# Schematic.net
KiCad netlist of a schematic drawn in EAGLE
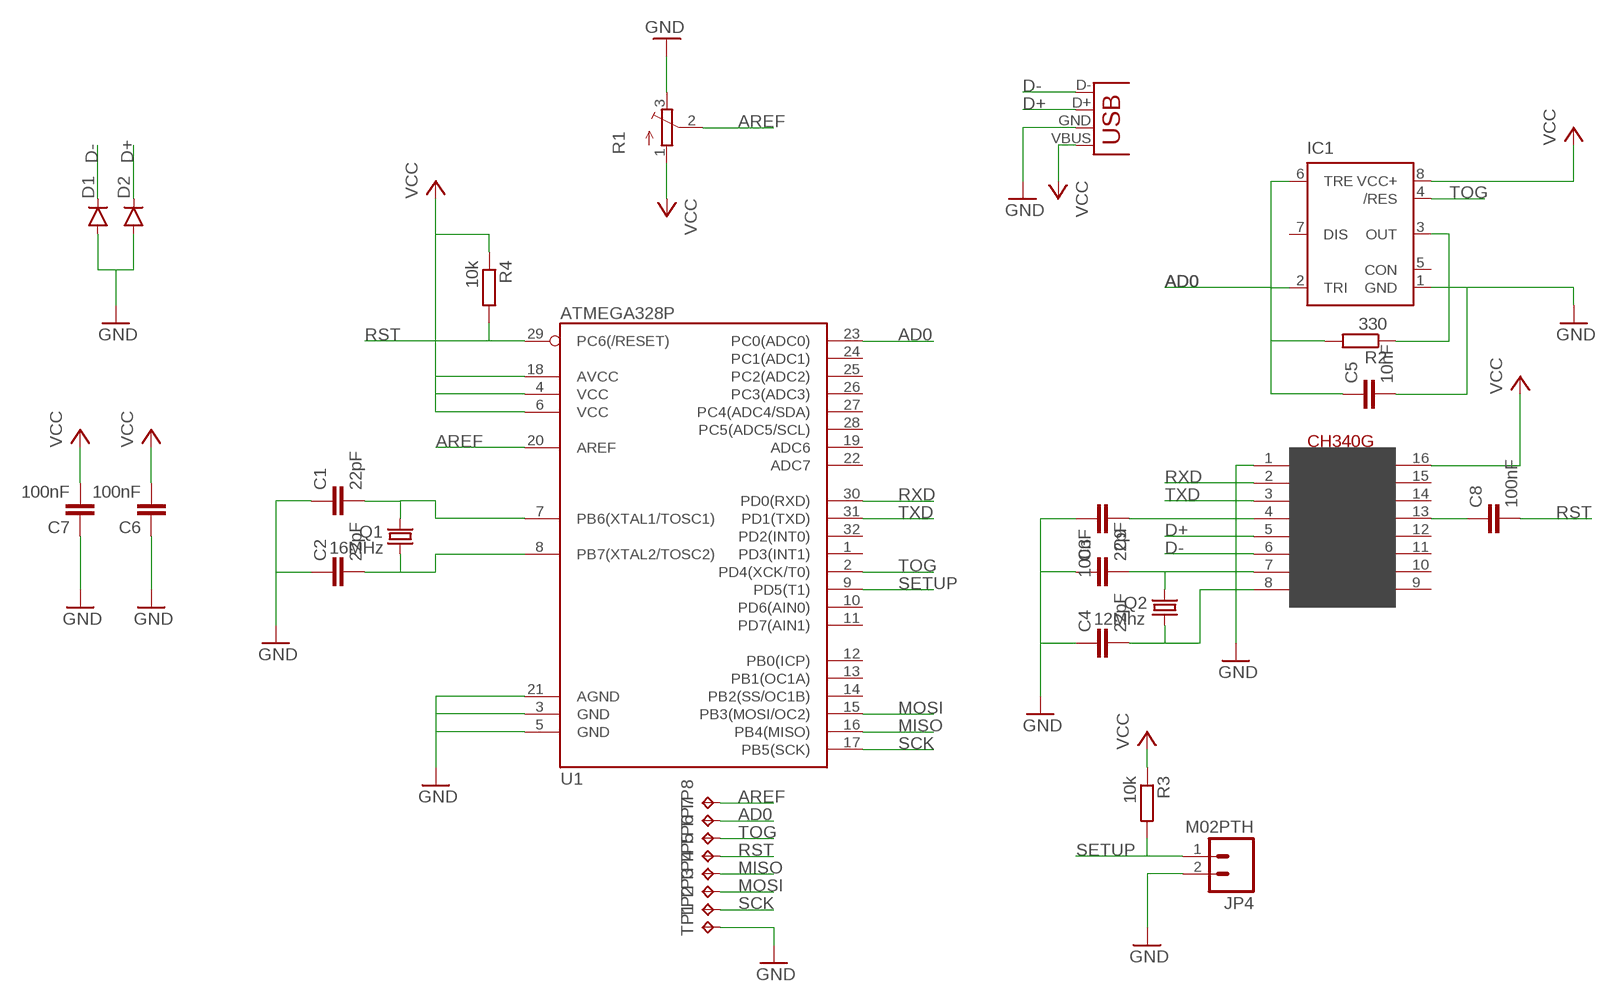
[diagram p0: schematic, sheet 1]

(export (version "E")
  (design (tool "Eeschema 10.0.6"))
  (components
    (comp (ref "C1")
      (value "22pF")
      (footprint "eagle-import:C0603K")
      (libsource (lib "eagle-import") (part "C-EUC0603K"))
    )
    (comp (ref "C2")
      (value "22pF")
      (footprint "eagle-import:C0603K")
      (libsource (lib "eagle-import") (part "C-EUC0603K"))
    )
    (comp (ref "C3")
      (value "22pF")
      (footprint "eagle-import:C0603K")
      (libsource (lib "eagle-import") (part "C-EUC0603K"))
    )
    (comp (ref "C4")
      (value "22pF")
      (footprint "eagle-import:C0603K")
      (libsource (lib "eagle-import") (part "C-EUC0603K"))
    )
    (comp (ref "C5")
      (value "10nF")
      (footprint "eagle-import:C0603K")
      (libsource (lib "eagle-import") (part "C-EUC0603K"))
    )
    (comp (ref "C6")
      (value "100nF")
      (footprint "eagle-import:C0603K")
      (libsource (lib "eagle-import") (part "C-EUC0603K"))
    )
    (comp (ref "C7")
      (value "100nF")
      (footprint "eagle-import:C0603K")
      (libsource (lib "eagle-import") (part "C-EUC0603K"))
    )
    (comp (ref "C8")
      (value "100nF")
      (footprint "eagle-import:C0603K")
      (libsource (lib "eagle-import") (part "C-EUC0603K"))
    )
    (comp (ref "C9")
      (value "100nF")
      (footprint "eagle-import:C0603K")
      (libsource (lib "eagle-import") (part "C-EUC0603K"))
    )
    (comp (ref "D1")
      (value "DIODESOD523")
      (footprint "eagle-import:SOD523")
      (libsource (lib "eagle-import") (part "DIODESOD523"))
    )
    (comp (ref "D2")
      (value "DIODESOD523")
      (footprint "eagle-import:SOD523")
      (libsource (lib "eagle-import") (part "DIODESOD523"))
    )
    (comp (ref "IC1")
      (value "NE555D")
      (footprint "eagle-import:SO08")
      (libsource (lib "eagle-import") (part "NE555D"))
    )
    (comp (ref "JP1")
      (value "USB-A-H")
      (footprint "eagle-import:USB-A-H")
      (libsource (lib "eagle-import") (part "USB-A-H"))
    )
    (comp (ref "JP4")
      (value "M02PTH")
      (footprint "eagle-import:1X02")
      (libsource (lib "eagle-import") (part "M02PTH"))
    )
    (comp (ref "Q1")
      (value "16MHz")
      (footprint "eagle-import:MT")
      (libsource (lib "eagle-import") (part "MT-OSCILLATOR"))
    )
    (comp (ref "Q2")
      (value "12Mhz")
      (footprint "eagle-import:MT")
      (libsource (lib "eagle-import") (part "MT-OSCILLATOR"))
    )
    (comp (ref "R1")
      (value "TRIM_EU-3223W")
      (footprint "eagle-import:3223W")
      (libsource (lib "eagle-import") (part "TRIM_EU-3223W"))
    )
    (comp (ref "R2")
      (value "330")
      (footprint "eagle-import:R0603")
      (libsource (lib "eagle-import") (part "R-EU_R0603"))
    )
    (comp (ref "R3")
      (value "10k")
      (footprint "eagle-import:R0603")
      (libsource (lib "eagle-import") (part "R-EU_R0603"))
    )
    (comp (ref "R4")
      (value "10k")
      (footprint "eagle-import:R0603")
      (libsource (lib "eagle-import") (part "R-EU_R0603"))
    )
    (comp (ref "TP1")
      (value "TPTP10R")
      (footprint "eagle-import:TP10R")
      (libsource (lib "eagle-import") (part "TPTP10R"))
    )
    (comp (ref "TP2")
      (value "TPTP10R")
      (footprint "eagle-import:TP10R")
      (libsource (lib "eagle-import") (part "TPTP10R"))
    )
    (comp (ref "TP3")
      (value "TPTP10R")
      (footprint "eagle-import:TP10R")
      (libsource (lib "eagle-import") (part "TPTP10R"))
    )
    (comp (ref "TP4")
      (value "TPTP10R")
      (footprint "eagle-import:TP10R")
      (libsource (lib "eagle-import") (part "TPTP10R"))
    )
    (comp (ref "TP5")
      (value "TPTP10R")
      (footprint "eagle-import:TP10R")
      (libsource (lib "eagle-import") (part "TPTP10R"))
    )
    (comp (ref "TP6")
      (value "TPTP10R")
      (footprint "eagle-import:TP10R")
      (libsource (lib "eagle-import") (part "TPTP10R"))
    )
    (comp (ref "TP7")
      (value "TPTP10R")
      (footprint "eagle-import:TP10R")
      (libsource (lib "eagle-import") (part "TPTP10R"))
    )
    (comp (ref "TP8")
      (value "TPTP10R")
      (footprint "eagle-import:TP10R")
      (libsource (lib "eagle-import") (part "TPTP10R"))
    )
    (comp (ref "U1")
      (value "ATMEGA328P")
      (footprint "eagle-import:TQFP32-08")
      (libsource (lib "eagle-import") (part "ATMEGA328_SMT"))
    )
    (comp (ref "U2")
      (value "CH340G")
      (footprint "eagle-import:SOIC16")
      (libsource (lib "eagle-import") (part "CH340G"))
    )
  )
  (nets
    (net (code "1") (name "/AD0") (class "Default")
      (node (ref "C5") (pin "1") (pinfunction "1_1") (pintype "passive"))
      (node (ref "IC1") (pin "2") (pinfunction "TRI_2") (pintype "input"))
      (node (ref "IC1") (pin "6") (pinfunction "TRE_6") (pintype "input"))
      (node (ref "R2") (pin "2") (pinfunction "2_2") (pintype "passive"))
      (node (ref "TP7") (pin "TP") (pinfunction "TP_TP") (pintype "input"))
      (node (ref "U1") (pin "23") (pinfunction "PC0(ADC0)_23") (pintype "bidirectional"))
    )
    (net (code "2") (name "/AREF") (class "Default")
      (node (ref "R1") (pin "2") (pinfunction "S_2") (pintype "passive"))
      (node (ref "TP8") (pin "TP") (pinfunction "TP_TP") (pintype "input"))
      (node (ref "U1") (pin "20") (pinfunction "AREF_20") (pintype "bidirectional"))
    )
    (net (code "3") (name "/D+") (class "Default")
      (node (ref "D2") (pin "C") (pinfunction "C_C") (pintype "passive"))
      (node (ref "JP1") (pin "D+") (pinfunction "D-_D+") (pintype "bidirectional"))
      (node (ref "U2") (pin "5") (pinfunction "D+_5") (pintype "bidirectional"))
    )
    (net (code "4") (name "/D-") (class "Default")
      (node (ref "D1") (pin "C") (pinfunction "C_C") (pintype "passive"))
      (node (ref "JP1") (pin "D-") (pinfunction "D+_D-") (pintype "bidirectional"))
      (node (ref "U2") (pin "6") (pinfunction "D-_6") (pintype "bidirectional"))
    )
    (net (code "5") (name "/MISO") (class "Default")
      (node (ref "TP4") (pin "TP") (pinfunction "TP_TP") (pintype "input"))
      (node (ref "U1") (pin "16") (pinfunction "PB4(MISO)_16") (pintype "bidirectional"))
    )
    (net (code "6") (name "/MOSI") (class "Default")
      (node (ref "TP3") (pin "TP") (pinfunction "TP_TP") (pintype "input"))
      (node (ref "U1") (pin "15") (pinfunction "PB3(MOSI/OC2)_15") (pintype "bidirectional"))
    )
    (net (code "7") (name "/RST") (class "Default")
      (node (ref "C8") (pin "2") (pinfunction "2_2") (pintype "passive"))
      (node (ref "R4") (pin "2") (pinfunction "2_2") (pintype "passive"))
      (node (ref "TP5") (pin "TP") (pinfunction "TP_TP") (pintype "input"))
      (node (ref "U1") (pin "29") (pinfunction "PC6(/RESET)_29") (pintype "bidirectional"))
    )
    (net (code "8") (name "/RXD") (class "Default")
      (node (ref "U1") (pin "30") (pinfunction "PD0(RXD)_30") (pintype "bidirectional"))
      (node (ref "U2") (pin "2") (pinfunction "TX_2") (pintype "bidirectional"))
    )
    (net (code "9") (name "/SCK") (class "Default")
      (node (ref "TP2") (pin "TP") (pinfunction "TP_TP") (pintype "input"))
      (node (ref "U1") (pin "17") (pinfunction "PB5(SCK)_17") (pintype "bidirectional"))
    )
    (net (code "10") (name "/SETUP") (class "Default")
      (node (ref "JP4") (pin "1") (pinfunction "1_1") (pintype "passive"))
      (node (ref "R3") (pin "2") (pinfunction "2_2") (pintype "passive"))
      (node (ref "U1") (pin "9") (pinfunction "PD5(T1)_9") (pintype "bidirectional"))
    )
    (net (code "11") (name "/TOG") (class "Default")
      (node (ref "IC1") (pin "4") (pinfunction "/RES_4") (pintype "input"))
      (node (ref "TP6") (pin "TP") (pinfunction "TP_TP") (pintype "input"))
      (node (ref "U1") (pin "2") (pinfunction "PD4(XCK/T0)_2") (pintype "bidirectional"))
    )
    (net (code "12") (name "/TXD") (class "Default")
      (node (ref "U1") (pin "31") (pinfunction "PD1(TXD)_31") (pintype "bidirectional"))
      (node (ref "U2") (pin "3") (pinfunction "RX_3") (pintype "bidirectional"))
    )
    (net (code "13") (name "GND") (class "Default")
      (node (ref "C1") (pin "1") (pinfunction "1_1") (pintype "passive"))
      (node (ref "C2") (pin "1") (pinfunction "1_1") (pintype "passive"))
      (node (ref "C3") (pin "1") (pinfunction "1_1") (pintype "passive"))
      (node (ref "C4") (pin "1") (pinfunction "1_1") (pintype "passive"))
      (node (ref "C5") (pin "2") (pinfunction "2_2") (pintype "passive"))
      (node (ref "C6") (pin "1") (pinfunction "1_1") (pintype "passive"))
      (node (ref "C7") (pin "1") (pinfunction "1_1") (pintype "passive"))
      (node (ref "C9") (pin "2") (pinfunction "2_2") (pintype "passive"))
      (node (ref "D1") (pin "A") (pinfunction "A_A") (pintype "passive"))
      (node (ref "D2") (pin "A") (pinfunction "A_A") (pintype "passive"))
      (node (ref "IC1") (pin "1") (pinfunction "GND_1") (pintype "power_in"))
      (node (ref "JP1") (pin "GND") (pinfunction "VBUS_GND") (pintype "bidirectional"))
      (node (ref "JP4") (pin "2") (pinfunction "2_2") (pintype "passive"))
      (node (ref "R1") (pin "3") (pinfunction "E_3") (pintype "passive"))
      (node (ref "TP1") (pin "TP") (pinfunction "TP_TP") (pintype "input"))
      (node (ref "U1") (pin "21") (pinfunction "AGND_21") (pintype "bidirectional"))
      (node (ref "U1") (pin "3") (pinfunction "GND_3") (pintype "bidirectional"))
      (node (ref "U1") (pin "5") (pinfunction "GND_5") (pintype "bidirectional"))
      (node (ref "U2") (pin "1") (pinfunction "GND_1") (pintype "bidirectional"))
    )
    (net (code "14") (name "Net-(IC1-OUT)") (class "Default")
      (node (ref "IC1") (pin "3") (pinfunction "OUT_3") (pintype "output"))
      (node (ref "R2") (pin "1") (pinfunction "1_1") (pintype "passive"))
    )
    (net (code "15") (name "Net-(Q1-2)") (class "Default")
      (node (ref "C1") (pin "2") (pinfunction "2_2") (pintype "passive"))
      (node (ref "Q1") (pin "3") (pinfunction "2_3") (pintype "passive"))
      (node (ref "U1") (pin "7") (pinfunction "PB6(XTAL1/TOSC1)_7") (pintype "bidirectional"))
    )
    (net (code "16") (name "Net-(Q2-2)") (class "Default")
      (node (ref "C3") (pin "2") (pinfunction "2_2") (pintype "passive"))
      (node (ref "Q2") (pin "3") (pinfunction "2_3") (pintype "passive"))
      (node (ref "U2") (pin "7") (pinfunction "XI_7") (pintype "bidirectional"))
    )
    (net (code "17") (name "Net-(U1-PB7(XTAL2{slash}TOSC2))") (class "Default")
      (node (ref "C2") (pin "2") (pinfunction "2_2") (pintype "passive"))
      (node (ref "Q1") (pin "1") (pinfunction "1_1") (pintype "passive"))
      (node (ref "U1") (pin "8") (pinfunction "PB7(XTAL2/TOSC2)_8") (pintype "bidirectional"))
    )
    (net (code "18") (name "Net-(U2-DTR)") (class "Default")
      (node (ref "C8") (pin "1") (pinfunction "1_1") (pintype "passive"))
      (node (ref "U2") (pin "13") (pinfunction "DTR_13") (pintype "bidirectional"))
    )
    (net (code "19") (name "Net-(U2-V3)") (class "Default")
      (node (ref "C9") (pin "1") (pinfunction "1_1") (pintype "passive"))
      (node (ref "U2") (pin "4") (pinfunction "V3_4") (pintype "bidirectional"))
    )
    (net (code "20") (name "Net-(U2-XO)") (class "Default")
      (node (ref "C4") (pin "2") (pinfunction "2_2") (pintype "passive"))
      (node (ref "Q2") (pin "1") (pinfunction "1_1") (pintype "passive"))
      (node (ref "U2") (pin "8") (pinfunction "XO_8") (pintype "bidirectional"))
    )
    (net (code "21") (name "VCC") (class "Default")
      (node (ref "C6") (pin "2") (pinfunction "2_2") (pintype "passive"))
      (node (ref "C7") (pin "2") (pinfunction "2_2") (pintype "passive"))
      (node (ref "IC1") (pin "8") (pinfunction "VCC+_8") (pintype "power_in"))
      (node (ref "JP1") (pin "VBUS") (pinfunction "GND_VBUS") (pintype "bidirectional"))
      (node (ref "R1") (pin "1") (pinfunction "A_1") (pintype "passive"))
      (node (ref "R3") (pin "1") (pinfunction "1_1") (pintype "passive"))
      (node (ref "R4") (pin "1") (pinfunction "1_1") (pintype "passive"))
      (node (ref "U1") (pin "18") (pinfunction "AVCC_18") (pintype "bidirectional"))
      (node (ref "U1") (pin "4") (pinfunction "VCC_4") (pintype "bidirectional"))
      (node (ref "U1") (pin "6") (pinfunction "VCC_6") (pintype "bidirectional"))
      (node (ref "U2") (pin "16") (pinfunction "VCC_16") (pintype "bidirectional"))
    )
    (net (code "22") (name "unconnected-(IC1-CON-Pad5)") (class "Default")
      (node (ref "IC1") (pin "5") (pinfunction "CON_5") (pintype "input"))
    )
    (net (code "23") (name "unconnected-(IC1-DIS-Pad7)") (class "Default")
      (node (ref "IC1") (pin "7") (pinfunction "DIS_7") (pintype "input"))
    )
    (net (code "24") (name "unconnected-(U1-ADC6-Pad19)") (class "Default")
      (node (ref "U1") (pin "19") (pinfunction "ADC6_19") (pintype "bidirectional"))
    )
    (net (code "25") (name "unconnected-(U1-ADC7-Pad22)") (class "Default")
      (node (ref "U1") (pin "22") (pinfunction "ADC7_22") (pintype "bidirectional"))
    )
    (net (code "26") (name "unconnected-(U1-PB0(ICP)-Pad12)") (class "Default")
      (node (ref "U1") (pin "12") (pinfunction "PB0(ICP)_12") (pintype "bidirectional"))
    )
    (net (code "27") (name "unconnected-(U1-PB1(OC1A)-Pad13)") (class "Default")
      (node (ref "U1") (pin "13") (pinfunction "PB1(OC1A)_13") (pintype "bidirectional"))
    )
    (net (code "28") (name "unconnected-(U1-PB2(SS{slash}OC1B)-Pad14)") (class "Default")
      (node (ref "U1") (pin "14") (pinfunction "PB2(SS/OC1B)_14") (pintype "bidirectional"))
    )
    (net (code "29") (name "unconnected-(U1-PC1(ADC1)-Pad24)") (class "Default")
      (node (ref "U1") (pin "24") (pinfunction "PC1(ADC1)_24") (pintype "bidirectional"))
    )
    (net (code "30") (name "unconnected-(U1-PC2(ADC2)-Pad25)") (class "Default")
      (node (ref "U1") (pin "25") (pinfunction "PC2(ADC2)_25") (pintype "bidirectional"))
    )
    (net (code "31") (name "unconnected-(U1-PC3(ADC3)-Pad26)") (class "Default")
      (node (ref "U1") (pin "26") (pinfunction "PC3(ADC3)_26") (pintype "bidirectional"))
    )
    (net (code "32") (name "unconnected-(U1-PC4(ADC4{slash}SDA)-Pad27)") (class "Default")
      (node (ref "U1") (pin "27") (pinfunction "PC4(ADC4/SDA)_27") (pintype "bidirectional"))
    )
    (net (code "33") (name "unconnected-(U1-PC5(ADC5{slash}SCL)-Pad28)") (class "Default")
      (node (ref "U1") (pin "28") (pinfunction "PC5(ADC5/SCL)_28") (pintype "bidirectional"))
    )
    (net (code "34") (name "unconnected-(U1-PD2(INT0)-Pad32)") (class "Default")
      (node (ref "U1") (pin "32") (pinfunction "PD2(INT0)_32") (pintype "bidirectional"))
    )
    (net (code "35") (name "unconnected-(U1-PD3(INT1)-Pad1)") (class "Default")
      (node (ref "U1") (pin "1") (pinfunction "PD3(INT1)_1") (pintype "bidirectional"))
    )
    (net (code "36") (name "unconnected-(U1-PD6(AIN0)-Pad10)") (class "Default")
      (node (ref "U1") (pin "10") (pinfunction "PD6(AIN0)_10") (pintype "bidirectional"))
    )
    (net (code "37") (name "unconnected-(U1-PD7(AIN1)-Pad11)") (class "Default")
      (node (ref "U1") (pin "11") (pinfunction "PD7(AIN1)_11") (pintype "bidirectional"))
    )
    (net (code "38") (name "unconnected-(U2-CTS-Pad9)") (class "Default")
      (node (ref "U2") (pin "9") (pinfunction "CTS_9") (pintype "bidirectional"))
    )
    (net (code "39") (name "unconnected-(U2-DCD-Pad12)") (class "Default")
      (node (ref "U2") (pin "12") (pinfunction "DCD_12") (pintype "bidirectional"))
    )
    (net (code "40") (name "unconnected-(U2-DSR-Pad10)") (class "Default")
      (node (ref "U2") (pin "10") (pinfunction "DSR_10") (pintype "bidirectional"))
    )
    (net (code "41") (name "unconnected-(U2-RI-Pad11)") (class "Default")
      (node (ref "U2") (pin "11") (pinfunction "RI_11") (pintype "bidirectional"))
    )
    (net (code "42") (name "unconnected-(U2-RS232-Pad15)") (class "Default")
      (node (ref "U2") (pin "15") (pinfunction "RS232_15") (pintype "bidirectional"))
    )
    (net (code "43") (name "unconnected-(U2-RTS-Pad14)") (class "Default")
      (node (ref "U2") (pin "14") (pinfunction "RTS_14") (pintype "bidirectional"))
    )
  )
)
